# network_analyzer.net
KiCad netlist of a schematic drawn in EAGLE
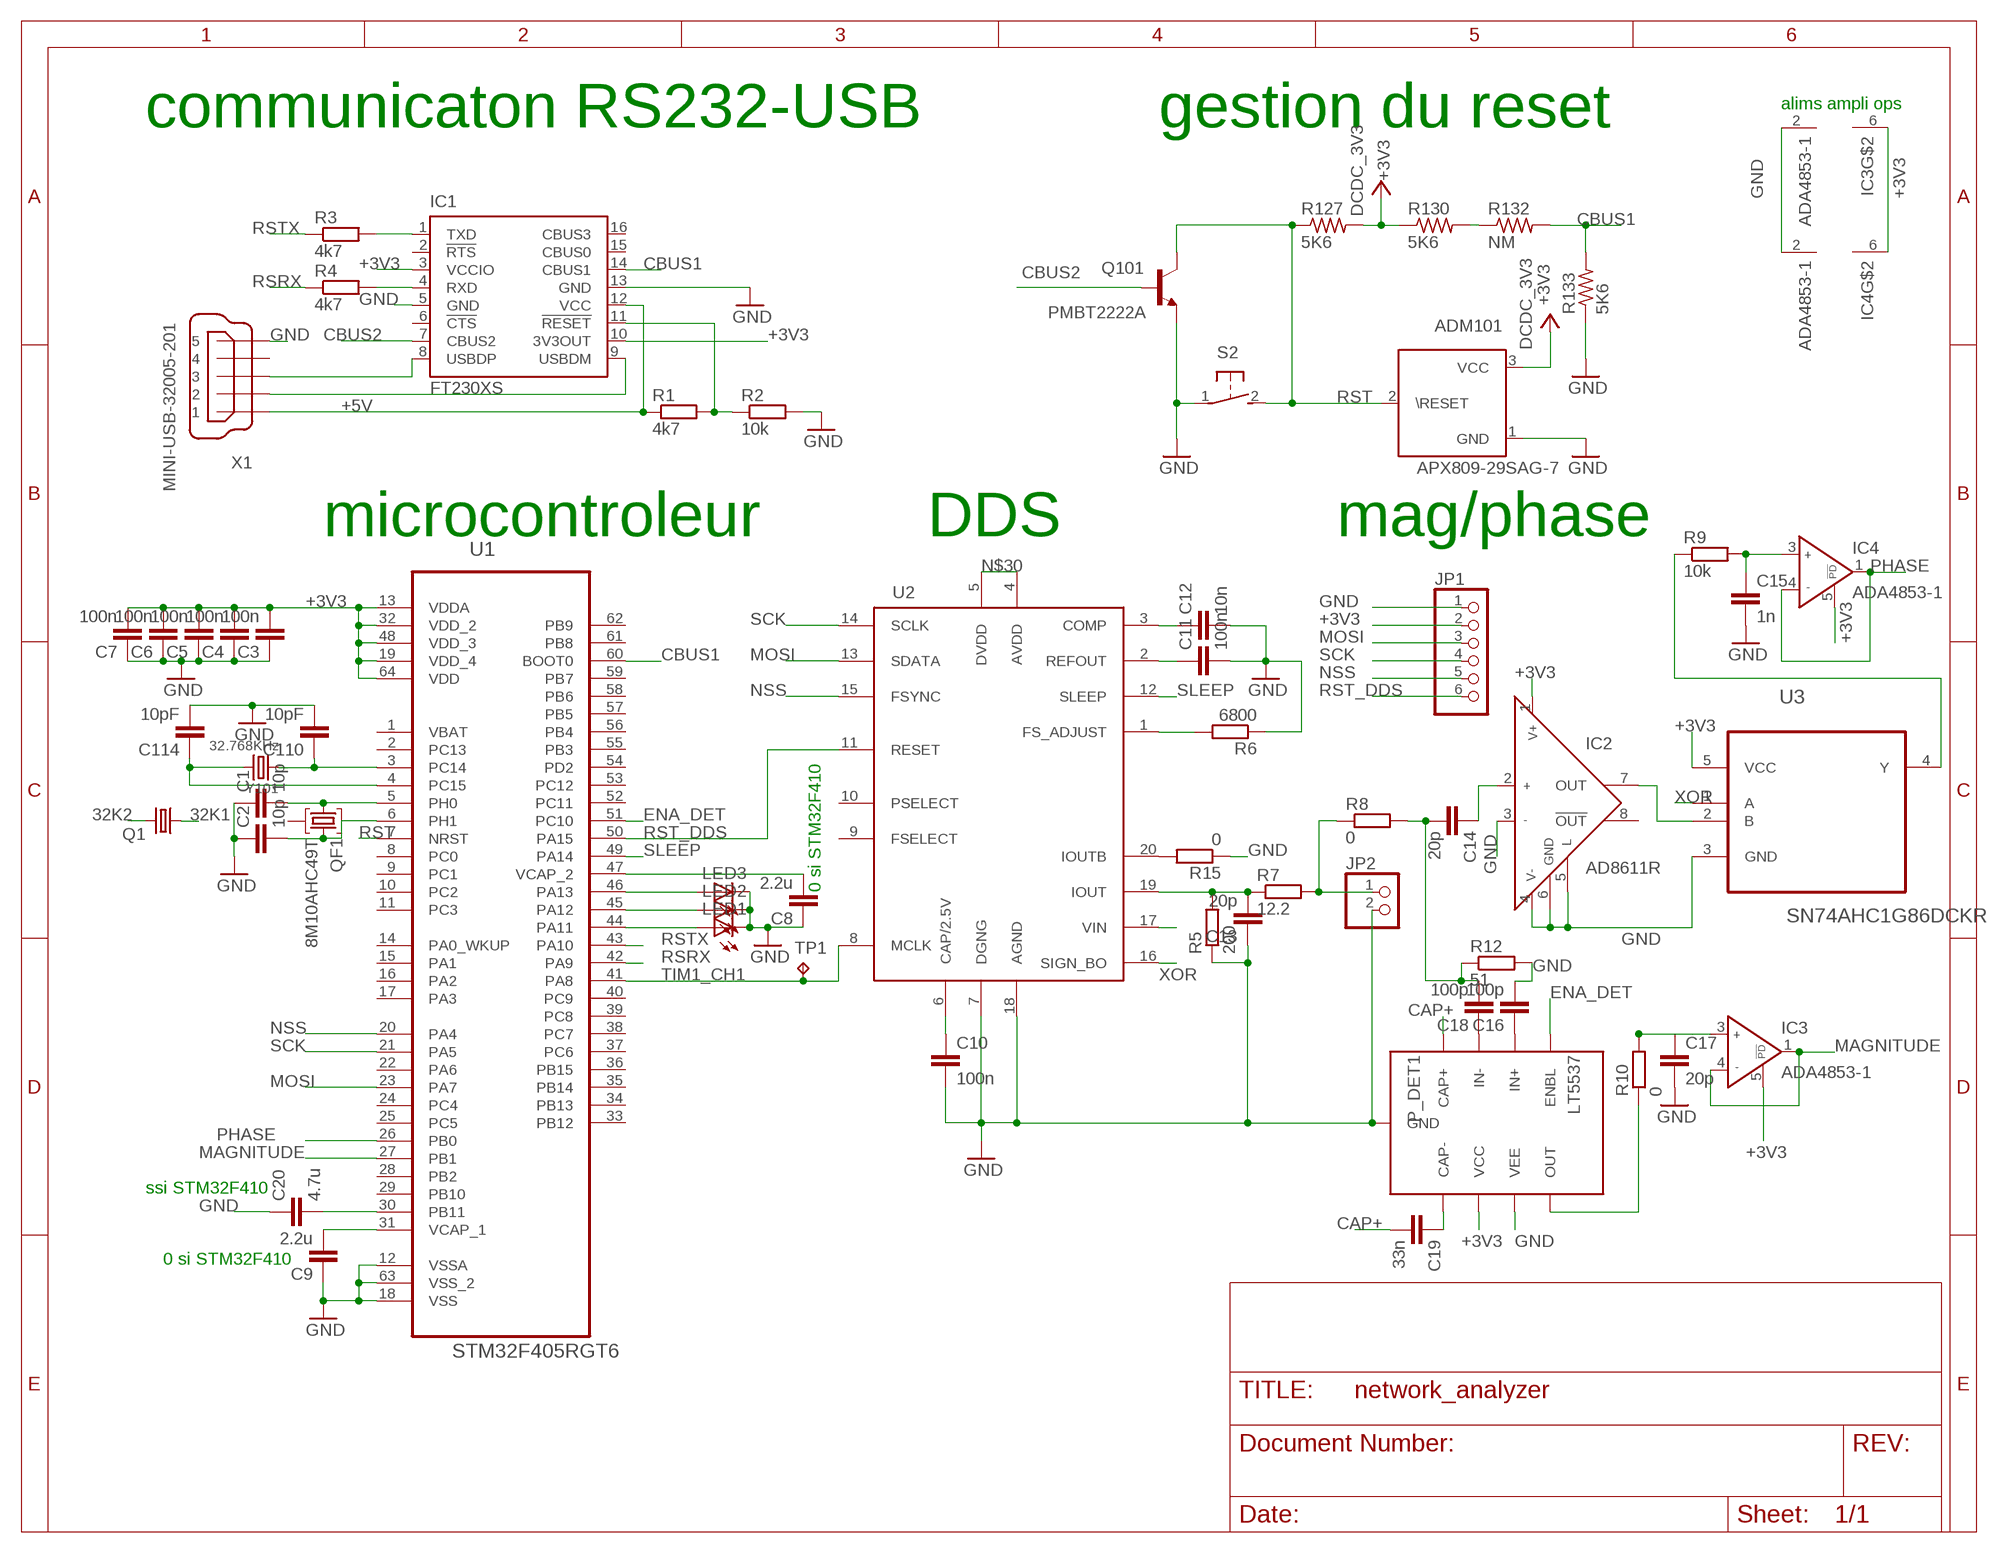
[diagram p0: schematic, sheet 1]

(export (version "E")
  (design (tool "Eeschema 10.0.6"))
  (components
    (comp (ref "ADM101")
      (value "APX809-29SAG-7")
      (footprint "eagle-import:CIS_SOT23_01")
      (fields (field (name "MANUFACTURER") "DIODES INC"))
      (libsource (lib "eagle-import") (part "APX809-29SAG-7"))
    )
    (comp (ref "C1")
      (value "10p")
      (footprint "eagle-import:C0603")
      (libsource (lib "eagle-import") (part "C-EUC0603"))
    )
    (comp (ref "C2")
      (value "10p")
      (footprint "eagle-import:C0603")
      (libsource (lib "eagle-import") (part "C-EUC0603"))
    )
    (comp (ref "C3")
      (value "100n")
      (footprint "eagle-import:C0603")
      (libsource (lib "eagle-import") (part "C-EUC0603"))
    )
    (comp (ref "C4")
      (value "100n")
      (footprint "eagle-import:C0603")
      (libsource (lib "eagle-import") (part "C-EUC0603"))
    )
    (comp (ref "C5")
      (value "100n")
      (footprint "eagle-import:C0603")
      (libsource (lib "eagle-import") (part "C-EUC0603"))
    )
    (comp (ref "C6")
      (value "100n")
      (footprint "eagle-import:C0603")
      (libsource (lib "eagle-import") (part "C-EUC0603"))
    )
    (comp (ref "C7")
      (value "100n")
      (footprint "eagle-import:C0603")
      (libsource (lib "eagle-import") (part "C-EUC0603"))
    )
    (comp (ref "C8")
      (value "2.2u")
      (footprint "eagle-import:C0402")
      (libsource (lib "eagle-import") (part "C-EUC0402"))
    )
    (comp (ref "C9")
      (value "2.2u")
      (footprint "eagle-import:C0402")
      (libsource (lib "eagle-import") (part "C-EUC0402"))
    )
    (comp (ref "C10")
      (value "100n")
      (footprint "eagle-import:C0603")
      (libsource (lib "eagle-import") (part "C-EUC0603"))
    )
    (comp (ref "C11")
      (value "100n")
      (footprint "eagle-import:C0603")
      (libsource (lib "eagle-import") (part "C-EUC0603"))
    )
    (comp (ref "C12")
      (value "10n")
      (footprint "eagle-import:C0603")
      (libsource (lib "eagle-import") (part "C-EUC0603"))
    )
    (comp (ref "C13")
      (value "20p")
      (footprint "eagle-import:C0603")
      (libsource (lib "eagle-import") (part "C-EUC0603"))
    )
    (comp (ref "C14")
      (value "20p")
      (footprint "eagle-import:C0603")
      (libsource (lib "eagle-import") (part "C-EUC0603"))
    )
    (comp (ref "C15")
      (value "1n")
      (footprint "eagle-import:C0603")
      (libsource (lib "eagle-import") (part "C-EUC0603"))
    )
    (comp (ref "C16")
      (value "100p")
      (footprint "eagle-import:C0603")
      (libsource (lib "eagle-import") (part "C-EUC0603"))
    )
    (comp (ref "C17")
      (value "20p")
      (footprint "eagle-import:C0603")
      (libsource (lib "eagle-import") (part "C-EUC0603"))
    )
    (comp (ref "C18")
      (value "100p")
      (footprint "eagle-import:C0603")
      (libsource (lib "eagle-import") (part "C-EUC0603"))
    )
    (comp (ref "C19")
      (value "33n")
      (footprint "eagle-import:C0603")
      (libsource (lib "eagle-import") (part "C-EUC0603"))
    )
    (comp (ref "C20")
      (value "4.7u")
      (footprint "eagle-import:C0603")
      (libsource (lib "eagle-import") (part "C-EUC0603"))
    )
    (comp (ref "C110")
      (value "10pF")
      (footprint "eagle-import:C0402")
      (fields (field (name "MANUFACTURER") "MURATA"))
      (libsource (lib "eagle-import") (part "GRM1555C1H100J"))
    )
    (comp (ref "C114")
      (value "10pF")
      (footprint "eagle-import:C0402")
      (fields (field (name "MANUFACTURER") "MURATA"))
      (libsource (lib "eagle-import") (part "GRM1555C1H100J"))
    )
    (comp (ref "IC1")
      (value "FT230XS")
      (footprint "eagle-import:SSOP16")
      (libsource (lib "eagle-import") (part "FT230XS"))
    )
    (comp (ref "IC2")
      (value "AD8611R")
      (footprint "eagle-import:SO8")
      (fields (field (name "MPN") "AD8611ARMZ-R2"))
      (libsource (lib "eagle-import") (part "AD8611R"))
    )
    (comp (ref "IC3")
      (value "ADA4853-1")
      (footprint "eagle-import:SC70-6")
      (libsource (lib "eagle-import") (part "ADA4853-1"))
    )
    (comp (ref "IC4")
      (value "ADA4853-1")
      (footprint "eagle-import:SC70-6")
      (libsource (lib "eagle-import") (part "ADA4853-1"))
    )
    (comp (ref "JP1")
      (value "PINHD-1X6")
      (footprint "eagle-import:1X06")
      (libsource (lib "eagle-import") (part "PINHD-1X6"))
    )
    (comp (ref "JP2")
      (value "PINHD-1X2")
      (footprint "eagle-import:1X02")
      (libsource (lib "eagle-import") (part "PINHD-1X2"))
    )
    (comp (ref "LED1")
      (value "LEDSML0603")
      (footprint "eagle-import:SML0603")
      (libsource (lib "eagle-import") (part "LEDSML0603"))
    )
    (comp (ref "LED2")
      (value "LEDSML0603")
      (footprint "eagle-import:SML0603")
      (libsource (lib "eagle-import") (part "LEDSML0603"))
    )
    (comp (ref "LED3")
      (value "LEDSML0603")
      (footprint "eagle-import:SML0603")
      (libsource (lib "eagle-import") (part "LEDSML0603"))
    )
    (comp (ref "P_DET1")
      (value "LT5537")
      (footprint "eagle-import:3X2MMDFN")
      (libsource (lib "eagle-import") (part "LT5537"))
    )
    (comp (ref "Q1")
      (value "CRYSTALTC26H")
      (footprint "eagle-import:TC26H")
      (libsource (lib "eagle-import") (part "CRYSTALTC26H"))
    )
    (comp (ref "Q101")
      (value "PMBT2222A")
      (footprint "eagle-import:Q-S_SOT23_01")
      (fields (field (name "MANUFACTURER") "NXP"))
      (libsource (lib "eagle-import") (part "PMBT2222A"))
    )
    (comp (ref "QF1")
      (value "8M10AHC49T")
      (footprint "eagle-import:HC49U")
      (libsource (lib "eagle-import") (part "8M10AHC49T"))
    )
    (comp (ref "R1")
      (value "4k7")
      (footprint "eagle-import:R0603")
      (libsource (lib "eagle-import") (part "R-EU_R0603"))
    )
    (comp (ref "R2")
      (value "10k")
      (footprint "eagle-import:R0603")
      (libsource (lib "eagle-import") (part "R-EU_R0603"))
    )
    (comp (ref "R3")
      (value "4k7")
      (footprint "eagle-import:R0603")
      (libsource (lib "eagle-import") (part "R-EU_R0603"))
    )
    (comp (ref "R4")
      (value "4k7")
      (footprint "eagle-import:R0603")
      (libsource (lib "eagle-import") (part "R-EU_R0603"))
    )
    (comp (ref "R5")
      (value "200")
      (footprint "eagle-import:R0603")
      (libsource (lib "eagle-import") (part "R-EU_R0603"))
    )
    (comp (ref "R6")
      (value "6800")
      (footprint "eagle-import:R0603")
      (libsource (lib "eagle-import") (part "R-EU_R0603"))
    )
    (comp (ref "R7")
      (value "12.2")
      (footprint "eagle-import:0207_10")
      (libsource (lib "eagle-import") (part "R-EU_0207/10"))
    )
    (comp (ref "R8")
      (value "0")
      (footprint "eagle-import:R0603")
      (libsource (lib "eagle-import") (part "R-EU_R0603"))
    )
    (comp (ref "R9")
      (value "10k")
      (footprint "eagle-import:R0603")
      (libsource (lib "eagle-import") (part "R-EU_R0603"))
    )
    (comp (ref "R10")
      (value "0")
      (footprint "eagle-import:R0603")
      (libsource (lib "eagle-import") (part "R-EU_R0603"))
    )
    (comp (ref "R12")
      (value "51")
      (footprint "eagle-import:R0603")
      (libsource (lib "eagle-import") (part "R-EU_R0603"))
    )
    (comp (ref "R15")
      (value "0")
      (footprint "eagle-import:R0603")
      (libsource (lib "eagle-import") (part "R-EU_R0603"))
    )
    (comp (ref "R127")
      (value "5K6")
      (footprint "eagle-import:R0402")
      (fields (field (name "MANUFACTURER") "PANASONIC"))
      (libsource (lib "eagle-import") (part "ERJ-2GEJ562X"))
    )
    (comp (ref "R130")
      (value "5K6")
      (footprint "eagle-import:R0402")
      (fields (field (name "MANUFACTURER") "PANASONIC"))
      (libsource (lib "eagle-import") (part "ERJ-2GEJ562X"))
    )
    (comp (ref "R132")
      (value "NM")
      (footprint "eagle-import:R0402")
      (libsource (lib "eagle-import") (part "R0402-NM"))
    )
    (comp (ref "R133")
      (value "5K6")
      (footprint "eagle-import:R0402")
      (fields (field (name "MANUFACTURER") "PANASONIC"))
      (libsource (lib "eagle-import") (part "ERJ-2GEJ562X"))
    )
    (comp (ref "S2")
      (value "31-XX")
      (footprint "eagle-import:B3F-31XX")
      (fields (field (name "MPN") "B3F-3100"))
      (libsource (lib "eagle-import") (part "31-XX"))
    )
    (comp (ref "TP1")
      (value "TPB1,27")
      (footprint "eagle-import:B1,27")
      (libsource (lib "eagle-import") (part "TPB1,27"))
    )
    (comp (ref "U1")
      (value "STM32F405RGT6")
      (footprint "eagle-import:QFP50P1200X1200X160-64N")
      (libsource (lib "eagle-import") (part "STM32F405RGT6"))
    )
    (comp (ref "U2")
      (value "AD9834")
      (footprint "eagle-import:TSSOP20")
      (libsource (lib "eagle-import") (part "?AD9834"))
    )
    (comp (ref "U3")
      (value "SN74AHC1G86DCKR")
      (footprint "eagle-import:SOT65P210X110-5N")
      (libsource (lib "eagle-import") (part "SN74AHC1G86DCKR"))
    )
    (comp (ref "X1")
      (value "MINI-USB-32005-201")
      (footprint "eagle-import:32005-201")
      (libsource (lib "eagle-import") (part "MINI-USB-32005-201"))
    )
    (comp (ref "Y101")
      (value "32.768KHz")
      (footprint "eagle-import:Y-S_3215_01")
      (fields (field (name "MANUFACTURER") "NDK"))
      (libsource (lib "eagle-import") (part "NX3215SA"))
    )
  )
  (nets
    (net (code "1") (name "/+5V") (class "Default")
      (node (ref "IC1") (pin "12") (pinfunction "VCC_12") (pintype "power_in"))
      (node (ref "R1") (pin "1") (pinfunction "1_1") (pintype "passive"))
      (node (ref "X1") (pin "1") (pinfunction "1_1") (pintype "passive"))
    )
    (net (code "2") (name "/32K1") (class "Default")
      (node (ref "C110") (pin "1") (pinfunction "1_1") (pintype "passive"))
      (node (ref "Q1") (pin "1") (pinfunction "1_1") (pintype "passive"))
      (node (ref "U1") (pin "3") (pinfunction "PC14_3") (pintype "bidirectional"))
      (node (ref "Y101") (pin "1") (pinfunction "1_1") (pintype "passive"))
    )
    (net (code "3") (name "/32K2") (class "Default")
      (node (ref "C114") (pin "1") (pinfunction "1_1") (pintype "passive"))
      (node (ref "Q1") (pin "2") (pinfunction "2_2") (pintype "passive"))
      (node (ref "U1") (pin "4") (pinfunction "PC15_4") (pintype "bidirectional"))
      (node (ref "Y101") (pin "2") (pinfunction "2_2") (pintype "passive"))
    )
    (net (code "4") (name "/CAP+") (class "Default")
      (node (ref "C19") (pin "2") (pinfunction "2_2") (pintype "passive"))
      (node (ref "P_DET1") (pin "P$4") (pinfunction "CAP+_P$4") (pintype "bidirectional"))
    )
    (net (code "5") (name "/CBUS1") (class "Default")
      (node (ref "IC1") (pin "14") (pinfunction "CBUS1_14") (pintype "bidirectional"))
      (node (ref "R132") (pin "2") (pinfunction "2_2") (pintype "passive"))
      (node (ref "R133") (pin "2") (pinfunction "2_2") (pintype "passive"))
      (node (ref "U1") (pin "60") (pinfunction "BOOT0_60") (pintype "passive"))
    )
    (net (code "6") (name "/CBUS2") (class "Default")
      (node (ref "IC1") (pin "7") (pinfunction "CBUS2_7") (pintype "bidirectional"))
      (node (ref "Q101") (pin "1") (pinfunction "B_1") (pintype "passive"))
    )
    (net (code "7") (name "/ENA_DET") (class "Default")
      (node (ref "P_DET1") (pin "P$1") (pinfunction "ENBL_P$1") (pintype "bidirectional"))
      (node (ref "U1") (pin "51") (pinfunction "PC10_51") (pintype "bidirectional"))
    )
    (net (code "8") (name "/MAGNITUDE") (class "Default")
      (node (ref "IC3") (pin "1") (pinfunction "OUT_1") (pintype "output"))
      (node (ref "IC3") (pin "4") (pinfunction "IN-_4") (pintype "input"))
      (node (ref "U1") (pin "27") (pinfunction "PB1_27") (pintype "bidirectional"))
    )
    (net (code "9") (name "/MOSI") (class "Default")
      (node (ref "JP1") (pin "3") (pinfunction "3_3") (pintype "passive"))
      (node (ref "U1") (pin "23") (pinfunction "PA7_23") (pintype "bidirectional"))
      (node (ref "U2") (pin "13") (pinfunction "SDATA_13") (pintype "input"))
    )
    (net (code "10") (name "/N$30") (class "Default")
      (node (ref "U2") (pin "4") (pinfunction "AVDD_4") (pintype "power_in"))
      (node (ref "U2") (pin "5") (pinfunction "DVDD_5") (pintype "power_in"))
    )
    (net (code "11") (name "/NSS") (class "Default")
      (node (ref "JP1") (pin "5") (pinfunction "5_5") (pintype "passive"))
      (node (ref "U1") (pin "20") (pinfunction "PA4_20") (pintype "bidirectional"))
      (node (ref "U2") (pin "15") (pinfunction "FSYNC_15") (pintype "input"))
    )
    (net (code "12") (name "/PHASE") (class "Default")
      (node (ref "IC4") (pin "1") (pinfunction "OUT_1") (pintype "output"))
      (node (ref "IC4") (pin "4") (pinfunction "IN-_4") (pintype "input"))
      (node (ref "U1") (pin "26") (pinfunction "PB0_26") (pintype "bidirectional"))
    )
    (net (code "13") (name "/RSRX") (class "Default")
      (node (ref "R4") (pin "1") (pinfunction "1_1") (pintype "passive"))
      (node (ref "U1") (pin "42") (pinfunction "PA9_42") (pintype "bidirectional"))
    )
    (net (code "14") (name "/RST") (class "Default")
      (node (ref "ADM101") (pin "2") (pinfunction "\\RESET_2") (pintype "passive"))
      (node (ref "Q101") (pin "3") (pinfunction "C_3") (pintype "passive"))
      (node (ref "R127") (pin "1") (pinfunction "1_1") (pintype "passive"))
      (node (ref "S2") (pin "2") (pinfunction "S_2") (pintype "passive"))
      (node (ref "U1") (pin "7") (pinfunction "NRST_7") (pintype "passive"))
    )
    (net (code "15") (name "/RSTX") (class "Default")
      (node (ref "R3") (pin "1") (pinfunction "1_1") (pintype "passive"))
      (node (ref "U1") (pin "43") (pinfunction "PA10_43") (pintype "bidirectional"))
    )
    (net (code "16") (name "/RST_DDS") (class "Default")
      (node (ref "JP1") (pin "6") (pinfunction "6_6") (pintype "passive"))
      (node (ref "U1") (pin "50") (pinfunction "PA15_50") (pintype "bidirectional"))
      (node (ref "U2") (pin "11") (pinfunction "RESET_11") (pintype "input"))
    )
    (net (code "17") (name "/SCK") (class "Default")
      (node (ref "JP1") (pin "4") (pinfunction "4_4") (pintype "passive"))
      (node (ref "U1") (pin "21") (pinfunction "PA5_21") (pintype "bidirectional"))
      (node (ref "U2") (pin "14") (pinfunction "SCLK_14") (pintype "input"))
    )
    (net (code "18") (name "/SLEEP") (class "Default")
      (node (ref "U1") (pin "49") (pinfunction "PA14_49") (pintype "bidirectional"))
      (node (ref "U2") (pin "12") (pinfunction "SLEEP_12") (pintype "input"))
    )
    (net (code "19") (name "/TIM1_CH1") (class "Default")
      (node (ref "TP1") (pin "TP") (pinfunction "TP_TP") (pintype "input"))
      (node (ref "U1") (pin "41") (pinfunction "PA8_41") (pintype "bidirectional"))
      (node (ref "U2") (pin "8") (pinfunction "MCLK_8") (pintype "input"))
    )
    (net (code "20") (name "/XOR") (class "Default")
      (node (ref "U2") (pin "16") (pinfunction "SIGN_BO_16") (pintype "output"))
      (node (ref "U3") (pin "1") (pinfunction "A_1") (pintype "input"))
    )
    (net (code "21") (name "DCDC_3V3") (class "Default")
      (node (ref "ADM101") (pin "3") (pinfunction "VCC_3") (pintype "passive"))
      (node (ref "C3") (pin "2") (pinfunction "2_2") (pintype "passive"))
      (node (ref "C4") (pin "2") (pinfunction "2_2") (pintype "passive"))
      (node (ref "C5") (pin "2") (pinfunction "2_2") (pintype "passive"))
      (node (ref "C6") (pin "2") (pinfunction "2_2") (pintype "passive"))
      (node (ref "C7") (pin "2") (pinfunction "2_2") (pintype "passive"))
      (node (ref "IC1") (pin "10") (pinfunction "3V3OUT_10") (pintype "output"))
      (node (ref "IC1") (pin "3") (pinfunction "VCCIO_3") (pintype "power_in"))
      (node (ref "IC2") (pin "1") (pinfunction "V+_1") (pintype "power_in"))
      (node (ref "IC3") (pin "5") (pinfunction "~{POWERDOWN}_5") (pintype "passive"))
      (node (ref "IC3") (pin "6") (pinfunction "V+_6") (pintype "power_in"))
      (node (ref "IC4") (pin "5") (pinfunction "~{POWERDOWN}_5") (pintype "passive"))
      (node (ref "IC4") (pin "6") (pinfunction "V+_6") (pintype "power_in"))
      (node (ref "JP1") (pin "2") (pinfunction "2_2") (pintype "passive"))
      (node (ref "P_DET1") (pin "P$6") (pinfunction "VCC_P$6") (pintype "bidirectional"))
      (node (ref "R127") (pin "2") (pinfunction "2_2") (pintype "passive"))
      (node (ref "R130") (pin "1") (pinfunction "1_1") (pintype "passive"))
      (node (ref "U1") (pin "13") (pinfunction "VDDA_13") (pintype "power_in"))
      (node (ref "U1") (pin "19") (pinfunction "VDD_4_19") (pintype "power_in"))
      (node (ref "U1") (pin "32") (pinfunction "VDD_2_32") (pintype "power_in"))
      (node (ref "U1") (pin "48") (pinfunction "VDD_3_48") (pintype "power_in"))
      (node (ref "U1") (pin "64") (pinfunction "VDD_64") (pintype "power_in"))
      (node (ref "U3") (pin "5") (pinfunction "VCC_5") (pintype "power_in"))
    )
    (net (code "22") (name "GND") (class "Default")
      (node (ref "ADM101") (pin "1") (pinfunction "GND_1") (pintype "passive"))
      (node (ref "C1") (pin "1") (pinfunction "1_1") (pintype "passive"))
      (node (ref "C10") (pin "2") (pinfunction "2_2") (pintype "passive"))
      (node (ref "C11") (pin "2") (pinfunction "2_2") (pintype "passive"))
      (node (ref "C110") (pin "2") (pinfunction "2_2") (pintype "passive"))
      (node (ref "C114") (pin "2") (pinfunction "2_2") (pintype "passive"))
      (node (ref "C12") (pin "2") (pinfunction "2_2") (pintype "passive"))
      (node (ref "C13") (pin "1") (pinfunction "1_1") (pintype "passive"))
      (node (ref "C15") (pin "2") (pinfunction "2_2") (pintype "passive"))
      (node (ref "C16") (pin "2") (pinfunction "2_2") (pintype "passive"))
      (node (ref "C17") (pin "2") (pinfunction "2_2") (pintype "passive"))
      (node (ref "C2") (pin "1") (pinfunction "1_1") (pintype "passive"))
      (node (ref "C20") (pin "1") (pinfunction "1_1") (pintype "passive"))
      (node (ref "C3") (pin "1") (pinfunction "1_1") (pintype "passive"))
      (node (ref "C4") (pin "1") (pinfunction "1_1") (pintype "passive"))
      (node (ref "C5") (pin "1") (pinfunction "1_1") (pintype "passive"))
      (node (ref "C6") (pin "1") (pinfunction "1_1") (pintype "passive"))
      (node (ref "C7") (pin "1") (pinfunction "1_1") (pintype "passive"))
      (node (ref "C8") (pin "1") (pinfunction "1_1") (pintype "passive"))
      (node (ref "C9") (pin "1") (pinfunction "1_1") (pintype "passive"))
      (node (ref "IC1") (pin "13") (pinfunction "GND_13") (pintype "power_in"))
      (node (ref "IC1") (pin "5") (pinfunction "GND_5") (pintype "power_in"))
      (node (ref "IC2") (pin "3") (pinfunction "IN-_3") (pintype "input"))
      (node (ref "IC2") (pin "4") (pinfunction "V-_4") (pintype "power_in"))
      (node (ref "IC2") (pin "5") (pinfunction "L_5") (pintype "input"))
      (node (ref "IC2") (pin "6") (pinfunction "GND_6") (pintype "power_in"))
      (node (ref "IC3") (pin "2") (pinfunction "V-_2") (pintype "power_in"))
      (node (ref "IC4") (pin "2") (pinfunction "V-_2") (pintype "power_in"))
      (node (ref "JP1") (pin "1") (pinfunction "1_1") (pintype "passive"))
      (node (ref "JP2") (pin "2") (pinfunction "2_2") (pintype "passive"))
      (node (ref "LED1") (pin "C") (pinfunction "C_C") (pintype "passive"))
      (node (ref "LED2") (pin "C") (pinfunction "C_C") (pintype "passive"))
      (node (ref "LED3") (pin "C") (pinfunction "C_C") (pintype "passive"))
      (node (ref "P_DET1") (pin "P$7") (pinfunction "VEE_P$7") (pintype "bidirectional"))
      (node (ref "P_DET1") (pin "P$9") (pinfunction "GND_P$9") (pintype "bidirectional"))
      (node (ref "Q101") (pin "2") (pinfunction "E_2") (pintype "passive"))
      (node (ref "R12") (pin "2") (pinfunction "2_2") (pintype "passive"))
      (node (ref "R133") (pin "1") (pinfunction "1_1") (pintype "passive"))
      (node (ref "R15") (pin "1") (pinfunction "1_1") (pintype "passive"))
      (node (ref "R2") (pin "2") (pinfunction "2_2") (pintype "passive"))
      (node (ref "R5") (pin "1") (pinfunction "1_1") (pintype "passive"))
      (node (ref "R6") (pin "1") (pinfunction "1_1") (pintype "passive"))
      (node (ref "S2") (pin "1") (pinfunction "P_1") (pintype "passive"))
      (node (ref "U1") (pin "12") (pinfunction "VSSA_12") (pintype "power_in"))
      (node (ref "U1") (pin "18") (pinfunction "VSS_18") (pintype "power_in"))
      (node (ref "U1") (pin "63") (pinfunction "VSS_2_63") (pintype "power_in"))
      (node (ref "U2") (pin "17") (pinfunction "VIN_17") (pintype "input"))
      (node (ref "U2") (pin "18") (pinfunction "AGND_18") (pintype "power_in"))
      (node (ref "U2") (pin "7") (pinfunction "DGNG_7") (pintype "power_in"))
      (node (ref "U3") (pin "3") (pinfunction "GND_3") (pintype "passive"))
      (node (ref "X1") (pin "5") (pinfunction "5_5") (pintype "passive"))
    )
    (net (code "23") (name "Net-(C14-Pad2)") (class "Default")
      (node (ref "C14") (pin "2") (pinfunction "2_2") (pintype "passive"))
      (node (ref "C18") (pin "2") (pinfunction "2_2") (pintype "passive"))
      (node (ref "R12") (pin "1") (pinfunction "1_1") (pintype "passive"))
      (node (ref "R8") (pin "2") (pinfunction "2_2") (pintype "passive"))
    )
    (net (code "24") (name "Net-(IC1-RXD)") (class "Default")
      (node (ref "IC1") (pin "4") (pinfunction "RXD_4") (pintype "input"))
      (node (ref "R4") (pin "2") (pinfunction "2_2") (pintype "passive"))
    )
    (net (code "25") (name "Net-(IC1-TXD)") (class "Default")
      (node (ref "IC1") (pin "1") (pinfunction "TXD_1") (pintype "output"))
      (node (ref "R3") (pin "2") (pinfunction "2_2") (pintype "passive"))
    )
    (net (code "26") (name "Net-(IC1-USBDM)") (class "Default")
      (node (ref "IC1") (pin "9") (pinfunction "USBDM_9") (pintype "input"))
      (node (ref "X1") (pin "2") (pinfunction "2_2") (pintype "passive"))
    )
    (net (code "27") (name "Net-(IC1-USBDP)") (class "Default")
      (node (ref "IC1") (pin "8") (pinfunction "USBDP_8") (pintype "input"))
      (node (ref "X1") (pin "3") (pinfunction "3_3") (pintype "passive"))
    )
    (net (code "28") (name "Net-(IC1-~{RESET})") (class "Default")
      (node (ref "IC1") (pin "11") (pinfunction "~{RESET}_11") (pintype "input"))
      (node (ref "R1") (pin "2") (pinfunction "2_2") (pintype "passive"))
      (node (ref "R2") (pin "1") (pinfunction "1_1") (pintype "passive"))
    )
    (net (code "29") (name "Net-(IC2-IN+)") (class "Default")
      (node (ref "C14") (pin "1") (pinfunction "1_1") (pintype "passive"))
      (node (ref "IC2") (pin "2") (pinfunction "IN+_2") (pintype "input"))
    )
    (net (code "30") (name "Net-(IC2-OUT)") (class "Default")
      (node (ref "IC2") (pin "7") (pinfunction "OUT_7") (pintype "output"))
      (node (ref "U3") (pin "2") (pinfunction "B_2") (pintype "input"))
    )
    (net (code "31") (name "Net-(IC3A-IN+)") (class "Default")
      (node (ref "C17") (pin "1") (pinfunction "1_1") (pintype "passive"))
      (node (ref "IC3") (pin "3") (pinfunction "IN+_3") (pintype "input"))
      (node (ref "R10") (pin "2") (pinfunction "2_2") (pintype "passive"))
    )
    (net (code "32") (name "Net-(IC4A-IN+)") (class "Default")
      (node (ref "C15") (pin "1") (pinfunction "1_1") (pintype "passive"))
      (node (ref "IC4") (pin "3") (pinfunction "IN+_3") (pintype "input"))
      (node (ref "R9") (pin "2") (pinfunction "2_2") (pintype "passive"))
    )
    (net (code "33") (name "Net-(JP2-Pad1)") (class "Default")
      (node (ref "JP2") (pin "1") (pinfunction "1_1") (pintype "passive"))
      (node (ref "R7") (pin "2") (pinfunction "2_2") (pintype "passive"))
      (node (ref "R8") (pin "1") (pinfunction "1_1") (pintype "passive"))
    )
    (net (code "34") (name "Net-(P_DET1-CAP-)") (class "Default")
      (node (ref "C19") (pin "1") (pinfunction "1_1") (pintype "passive"))
      (node (ref "P_DET1") (pin "P$5") (pinfunction "CAP-_P$5") (pintype "bidirectional"))
    )
    (net (code "35") (name "Net-(P_DET1-IN+)") (class "Default")
      (node (ref "C16") (pin "1") (pinfunction "1_1") (pintype "passive"))
      (node (ref "P_DET1") (pin "P$2") (pinfunction "IN+_P$2") (pintype "bidirectional"))
    )
    (net (code "36") (name "Net-(P_DET1-IN-)") (class "Default")
      (node (ref "C18") (pin "1") (pinfunction "1_1") (pintype "passive"))
      (node (ref "P_DET1") (pin "P$3") (pinfunction "IN-_P$3") (pintype "bidirectional"))
    )
    (net (code "37") (name "Net-(P_DET1-OUT)") (class "Default")
      (node (ref "P_DET1") (pin "P$8") (pinfunction "OUT_P$8") (pintype "bidirectional"))
      (node (ref "R10") (pin "1") (pinfunction "1_1") (pintype "passive"))
    )
    (net (code "38") (name "Net-(R130-Pad2)") (class "Default")
      (node (ref "R130") (pin "2") (pinfunction "2_2") (pintype "passive"))
      (node (ref "R132") (pin "1") (pinfunction "1_1") (pintype "passive"))
    )
    (net (code "39") (name "Net-(U1-PA11)") (class "Default")
      (node (ref "LED1") (pin "A") (pinfunction "A_A") (pintype "passive"))
      (node (ref "U1") (pin "44") (pinfunction "PA11_44") (pintype "bidirectional"))
    )
    (net (code "40") (name "Net-(U1-PA12)") (class "Default")
      (node (ref "LED2") (pin "A") (pinfunction "A_A") (pintype "passive"))
      (node (ref "U1") (pin "45") (pinfunction "PA12_45") (pintype "bidirectional"))
    )
    (net (code "41") (name "Net-(U1-PA13)") (class "Default")
      (node (ref "LED3") (pin "A") (pinfunction "A_A") (pintype "passive"))
      (node (ref "U1") (pin "46") (pinfunction "PA13_46") (pintype "bidirectional"))
    )
    (net (code "42") (name "Net-(U1-PB11)") (class "Default")
      (node (ref "C20") (pin "2") (pinfunction "2_2") (pintype "passive"))
      (node (ref "U1") (pin "30") (pinfunction "PB11_30") (pintype "bidirectional"))
    )
    (net (code "43") (name "Net-(U1-PH0)") (class "Default")
      (node (ref "C1") (pin "2") (pinfunction "2_2") (pintype "passive"))
      (node (ref "QF1") (pin "1") (pinfunction "1_1") (pintype "passive"))
      (node (ref "U1") (pin "5") (pinfunction "PH0_5") (pintype "bidirectional"))
    )
    (net (code "44") (name "Net-(U1-PH1)") (class "Default")
      (node (ref "C2") (pin "2") (pinfunction "2_2") (pintype "passive"))
      (node (ref "QF1") (pin "3") (pinfunction "3_3") (pintype "passive"))
      (node (ref "U1") (pin "6") (pinfunction "PH1_6") (pintype "bidirectional"))
    )
    (net (code "45") (name "Net-(U1-VCAP_1)") (class "Default")
      (node (ref "C9") (pin "2") (pinfunction "2_2") (pintype "passive"))
      (node (ref "U1") (pin "31") (pinfunction "VCAP_1_31") (pintype "passive"))
    )
    (net (code "46") (name "Net-(U1-VCAP_2)") (class "Default")
      (node (ref "C8") (pin "2") (pinfunction "2_2") (pintype "passive"))
      (node (ref "U1") (pin "47") (pinfunction "VCAP_2_47") (pintype "passive"))
    )
    (net (code "47") (name "Net-(U2-CAP{slash}2.5V)") (class "Default")
      (node (ref "C10") (pin "1") (pinfunction "1_1") (pintype "passive"))
      (node (ref "U2") (pin "6") (pinfunction "CAP/2.5V_6") (pintype "bidirectional"))
    )
    (net (code "48") (name "Net-(U2-COMP)") (class "Default")
      (node (ref "C12") (pin "1") (pinfunction "1_1") (pintype "passive"))
      (node (ref "U2") (pin "3") (pinfunction "COMP_3") (pintype "bidirectional"))
    )
    (net (code "49") (name "Net-(U2-FS_ADJUST)") (class "Default")
      (node (ref "R6") (pin "2") (pinfunction "2_2") (pintype "passive"))
      (node (ref "U2") (pin "1") (pinfunction "FS_ADJUST_1") (pintype "bidirectional"))
    )
    (net (code "50") (name "Net-(U2-IOUT)") (class "Default")
      (node (ref "C13") (pin "2") (pinfunction "2_2") (pintype "passive"))
      (node (ref "R5") (pin "2") (pinfunction "2_2") (pintype "passive"))
      (node (ref "R7") (pin "1") (pinfunction "1_1") (pintype "passive"))
      (node (ref "U2") (pin "19") (pinfunction "IOUT_19") (pintype "output"))
    )
    (net (code "51") (name "Net-(U2-IOUTB)") (class "Default")
      (node (ref "R15") (pin "2") (pinfunction "2_2") (pintype "passive"))
      (node (ref "U2") (pin "20") (pinfunction "IOUTB_20") (pintype "output"))
    )
    (net (code "52") (name "Net-(U2-REFOUT)") (class "Default")
      (node (ref "C11") (pin "1") (pinfunction "1_1") (pintype "passive"))
      (node (ref "U2") (pin "2") (pinfunction "REFOUT_2") (pintype "bidirectional"))
    )
    (net (code "53") (name "Net-(U3-Y)") (class "Default")
      (node (ref "R9") (pin "1") (pinfunction "1_1") (pintype "passive"))
      (node (ref "U3") (pin "4") (pinfunction "Y_4") (pintype "output"))
    )
    (net (code "54") (name "unconnected-(IC1-CBUS0-Pad15)") (class "Default")
      (node (ref "IC1") (pin "15") (pinfunction "CBUS0_15") (pintype "bidirectional"))
    )
    (net (code "55") (name "unconnected-(IC1-CBUS3-Pad16)") (class "Default")
      (node (ref "IC1") (pin "16") (pinfunction "CBUS3_16") (pintype "bidirectional"))
    )
    (net (code "56") (name "unconnected-(IC1-~{CTS}-Pad6)") (class "Default")
      (node (ref "IC1") (pin "6") (pinfunction "~{CTS}_6") (pintype "input"))
    )
    (net (code "57") (name "unconnected-(IC1-~{RTS}-Pad2)") (class "Default")
      (node (ref "IC1") (pin "2") (pinfunction "~{RTS}_2") (pintype "output"))
    )
    (net (code "58") (name "unconnected-(IC2-~{OUT}-Pad8)") (class "Default")
      (node (ref "IC2") (pin "8") (pinfunction "~{OUT}_8") (pintype "output"))
    )
    (net (code "59") (name "unconnected-(QF1-Pad2)") (class "Default")
      (node (ref "QF1") (pin "2") (pinfunction "2_2") (pintype "passive"))
    )
    (net (code "60") (name "unconnected-(U1-PA0_WKUP-Pad14)") (class "Default")
      (node (ref "U1") (pin "14") (pinfunction "PA0_WKUP_14") (pintype "passive"))
    )
    (net (code "61") (name "unconnected-(U1-PA1-Pad15)") (class "Default")
      (node (ref "U1") (pin "15") (pinfunction "PA1_15") (pintype "bidirectional"))
    )
    (net (code "62") (name "unconnected-(U1-PA2-Pad16)") (class "Default")
      (node (ref "U1") (pin "16") (pinfunction "PA2_16") (pintype "bidirectional"))
    )
    (net (code "63") (name "unconnected-(U1-PA3-Pad17)") (class "Default")
      (node (ref "U1") (pin "17") (pinfunction "PA3_17") (pintype "bidirectional"))
    )
    (net (code "64") (name "unconnected-(U1-PA6-Pad22)") (class "Default")
      (node (ref "U1") (pin "22") (pinfunction "PA6_22") (pintype "bidirectional"))
    )
    (net (code "65") (name "unconnected-(U1-PB2-Pad28)") (class "Default")
      (node (ref "U1") (pin "28") (pinfunction "PB2_28") (pintype "bidirectional"))
    )
    (net (code "66") (name "unconnected-(U1-PB3-Pad55)") (class "Default")
      (node (ref "U1") (pin "55") (pinfunction "PB3_55") (pintype "bidirectional"))
    )
    (net (code "67") (name "unconnected-(U1-PB4-Pad56)") (class "Default")
      (node (ref "U1") (pin "56") (pinfunction "PB4_56") (pintype "bidirectional"))
    )
    (net (code "68") (name "unconnected-(U1-PB5-Pad57)") (class "Default")
      (node (ref "U1") (pin "57") (pinfunction "PB5_57") (pintype "bidirectional"))
    )
    (net (code "69") (name "unconnected-(U1-PB6-Pad58)") (class "Default")
      (node (ref "U1") (pin "58") (pinfunction "PB6_58") (pintype "bidirectional"))
    )
    (net (code "70") (name "unconnected-(U1-PB7-Pad59)") (class "Default")
      (node (ref "U1") (pin "59") (pinfunction "PB7_59") (pintype "bidirectional"))
    )
    (net (code "71") (name "unconnected-(U1-PB8-Pad61)") (class "Default")
      (node (ref "U1") (pin "61") (pinfunction "PB8_61") (pintype "bidirectional"))
    )
    (net (code "72") (name "unconnected-(U1-PB9-Pad62)") (class "Default")
      (node (ref "U1") (pin "62") (pinfunction "PB9_62") (pintype "bidirectional"))
    )
    (net (code "73") (name "unconnected-(U1-PB10-Pad29)") (class "Default")
      (node (ref "U1") (pin "29") (pinfunction "PB10_29") (pintype "bidirectional"))
    )
    (net (code "74") (name "unconnected-(U1-PB12-Pad33)") (class "Default")
      (node (ref "U1") (pin "33") (pinfunction "PB12_33") (pintype "bidirectional"))
    )
    (net (code "75") (name "unconnected-(U1-PB13-Pad34)") (class "Default")
      (node (ref "U1") (pin "34") (pinfunction "PB13_34") (pintype "bidirectional"))
    )
    (net (code "76") (name "unconnected-(U1-PB14-Pad35)") (class "Default")
      (node (ref "U1") (pin "35") (pinfunction "PB14_35") (pintype "bidirectional"))
    )
    (net (code "77") (name "unconnected-(U1-PB15-Pad36)") (class "Default")
      (node (ref "U1") (pin "36") (pinfunction "PB15_36") (pintype "bidirectional"))
    )
    (net (code "78") (name "unconnected-(U1-PC0-Pad8)") (class "Default")
      (node (ref "U1") (pin "8") (pinfunction "PC0_8") (pintype "bidirectional"))
    )
    (net (code "79") (name "unconnected-(U1-PC1-Pad9)") (class "Default")
      (node (ref "U1") (pin "9") (pinfunction "PC1_9") (pintype "bidirectional"))
    )
    (net (code "80") (name "unconnected-(U1-PC2-Pad10)") (class "Default")
      (node (ref "U1") (pin "10") (pinfunction "PC2_10") (pintype "bidirectional"))
    )
    (net (code "81") (name "unconnected-(U1-PC3-Pad11)") (class "Default")
      (node (ref "U1") (pin "11") (pinfunction "PC3_11") (pintype "bidirectional"))
    )
    (net (code "82") (name "unconnected-(U1-PC4-Pad24)") (class "Default")
      (node (ref "U1") (pin "24") (pinfunction "PC4_24") (pintype "bidirectional"))
    )
    (net (code "83") (name "unconnected-(U1-PC5-Pad25)") (class "Default")
      (node (ref "U1") (pin "25") (pinfunction "PC5_25") (pintype "bidirectional"))
    )
    (net (code "84") (name "unconnected-(U1-PC6-Pad37)") (class "Default")
      (node (ref "U1") (pin "37") (pinfunction "PC6_37") (pintype "bidirectional"))
    )
    (net (code "85") (name "unconnected-(U1-PC7-Pad38)") (class "Default")
      (node (ref "U1") (pin "38") (pinfunction "PC7_38") (pintype "bidirectional"))
    )
    (net (code "86") (name "unconnected-(U1-PC8-Pad39)") (class "Default")
      (node (ref "U1") (pin "39") (pinfunction "PC8_39") (pintype "bidirectional"))
    )
    (net (code "87") (name "unconnected-(U1-PC9-Pad40)") (class "Default")
      (node (ref "U1") (pin "40") (pinfunction "PC9_40") (pintype "bidirectional"))
    )
    (net (code "88") (name "unconnected-(U1-PC11-Pad52)") (class "Default")
      (node (ref "U1") (pin "52") (pinfunction "PC11_52") (pintype "bidirectional"))
    )
    (net (code "89") (name "unconnected-(U1-PC12-Pad53)") (class "Default")
      (node (ref "U1") (pin "53") (pinfunction "PC12_53") (pintype "bidirectional"))
    )
    (net (code "90") (name "unconnected-(U1-PC13-Pad2)") (class "Default")
      (node (ref "U1") (pin "2") (pinfunction "PC13_2") (pintype "bidirectional"))
    )
    (net (code "91") (name "unconnected-(U1-PD2-Pad54)") (class "Default")
      (node (ref "U1") (pin "54") (pinfunction "PD2_54") (pintype "bidirectional"))
    )
    (net (code "92") (name "unconnected-(U1-VBAT-Pad1)") (class "Default")
      (node (ref "U1") (pin "1") (pinfunction "VBAT_1") (pintype "passive"))
    )
    (net (code "93") (name "unconnected-(U2-FSELECT-Pad9)") (class "Default")
      (node (ref "U2") (pin "9") (pinfunction "FSELECT_9") (pintype "input"))
    )
    (net (code "94") (name "unconnected-(U2-PSELECT-Pad10)") (class "Default")
      (node (ref "U2") (pin "10") (pinfunction "PSELECT_10") (pintype "input"))
    )
    (net (code "95") (name "unconnected-(X1-Pad4)") (class "Default")
      (node (ref "X1") (pin "4") (pinfunction "4_4") (pintype "passive"))
    )
  )
)
